# 24V_to_5V.net
KiCad netlist of a schematic drawn in Altium Designer
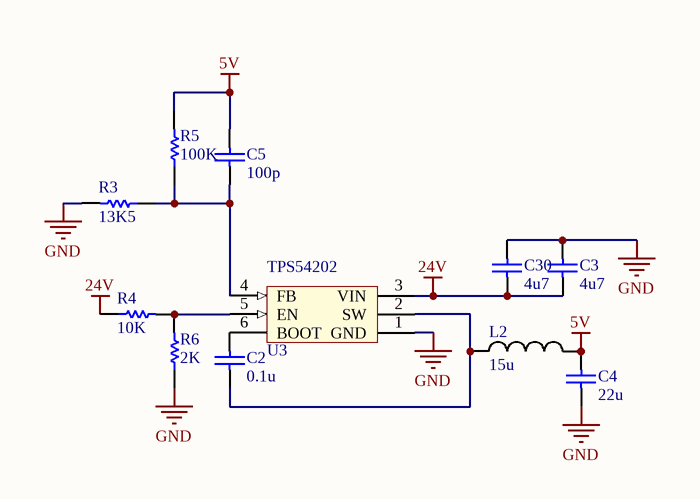
[diagram p0: 24V_to_5V.SchDoc]

(export (version "E")
  (design (tool "Eeschema 10.0.6"))
  (components
    (comp (ref "C2")
      (value "0.1u")
      (footprint "CAPC1608X90N")
      (description "Capacitor")
      (fields (field (name "Comment") "Cap") (field (name "PUBLISHER") "Altium Limited"))
      (libsource (lib "IOBoard_Low") (part "Cap"))
    )
    (comp (ref "C3")
      (value "4u7")
      (footprint "CAPC2012X135N")
      (description "Capacitor")
      (fields (field (name "Comment") "Cap") (field (name "PUBLISHER") "Altium Limited"))
      (libsource (lib "IOBoard_Low") (part "Cap"))
    )
    (comp (ref "C4")
      (value "22u")
      (footprint "CAPC2012X135N")
      (description "Capacitor")
      (fields (field (name "Comment") "Cap") (field (name "PUBLISHER") "Altium Limited"))
      (libsource (lib "IOBoard_Low") (part "Cap"))
    )
    (comp (ref "C5")
      (value "100p")
      (footprint "CAPC1608X90N")
      (description "Capacitor")
      (fields (field (name "Comment") "Cap") (field (name "PUBLISHER") "Altium Limited"))
      (libsource (lib "IOBoard_Low") (part "Cap"))
    )
    (comp (ref "C30")
      (value "4u7")
      (footprint "CAPC2012X135N")
      (description "Capacitor")
      (fields (field (name "Comment") "Cap") (field (name "PUBLISHER") "Altium Limited"))
      (libsource (lib "IOBoard_Low") (part "Cap"))
    )
    (comp (ref "L2")
      (value "15u")
      (footprint "INDC_5.5x5.3x3")
      (description "15uH inductor with 2A saturation current. Dimension is 5.5 * 5.2 * 3 mm^3")
      (fields (field (name "Comment") "15uH inductor"))
      (libsource (lib "IOBoard_Low") (part "INDC_MPX1D0530L150"))
    )
    (comp (ref "R3")
      (value "13K5")
      (footprint "RESC1608X55N")
      (description "Resistor")
      (fields (field (name "Comment") "Res1") (field (name "PUBLISHER") "Altium Limited"))
      (libsource (lib "IOBoard_Low") (part "Res1"))
    )
    (comp (ref "R4")
      (value "10K")
      (footprint "RESC1608X55N")
      (description "Resistor")
      (fields (field (name "Comment") "Res1") (field (name "PUBLISHER") "Altium Limited"))
      (libsource (lib "IOBoard_Low") (part "Res1"))
    )
    (comp (ref "R5")
      (value "100K")
      (footprint "RESC1608X55N")
      (description "Resistor")
      (fields (field (name "Comment") "Res1") (field (name "PUBLISHER") "Altium Limited"))
      (libsource (lib "IOBoard_Low") (part "Res1"))
    )
    (comp (ref "R6")
      (value "2K")
      (footprint "RESC1608X55N")
      (description "Resistor")
      (fields (field (name "Comment") "Res1") (field (name "PUBLISHER") "Altium Limited"))
      (libsource (lib "IOBoard_Low") (part "Res1"))
    )
    (comp (ref "U3")
      (value "TPS54202")
      (footprint "SOT23-6")
      (description "4.5-28V input 2A output step down, EMI Friendly Synchronous Step Down Converter")
      (libsource (lib "IOBoard_Low") (part "TPS54202"))
    )
  )
  (nets
    (net (code "1") (name "5V") (class "Default")
      (node (ref "C4") (pin "2") (pinfunction "2_2") (pintype "passive"))
      (node (ref "C5") (pin "2") (pinfunction "2_2") (pintype "passive"))
      (node (ref "L2") (pin "2") (pinfunction "2_2") (pintype "passive"))
      (node (ref "R5") (pin "2") (pinfunction "2_2") (pintype "passive"))
    )
    (net (code "2") (name "24V") (class "Default")
      (node (ref "C3") (pin "2") (pinfunction "2_2") (pintype "passive"))
      (node (ref "C30") (pin "2") (pinfunction "2_2") (pintype "passive"))
      (node (ref "R4") (pin "1") (pinfunction "1_1") (pintype "passive"))
      (node (ref "U3") (pin "3") (pinfunction "VIN_3") (pintype "power_in"))
    )
    (net (code "3") (name "GND") (class "Default")
      (node (ref "C3") (pin "1") (pinfunction "1_1") (pintype "passive"))
      (node (ref "C30") (pin "1") (pinfunction "1_1") (pintype "passive"))
      (node (ref "C4") (pin "1") (pinfunction "1_1") (pintype "passive"))
      (node (ref "R3") (pin "2") (pinfunction "2_2") (pintype "passive"))
      (node (ref "R6") (pin "1") (pinfunction "1_1") (pintype "passive"))
      (node (ref "U3") (pin "1") (pinfunction "GND_1") (pintype "power_in"))
    )
    (net (code "4") (name "Net-(U3-BOOT)") (class "Default")
      (node (ref "C2") (pin "2") (pinfunction "2_2") (pintype "passive"))
      (node (ref "U3") (pin "6") (pinfunction "BOOT_6") (pintype "passive"))
    )
    (net (code "5") (name "Net-(U3-EN)") (class "Default")
      (node (ref "R4") (pin "2") (pinfunction "2_2") (pintype "passive"))
      (node (ref "R6") (pin "2") (pinfunction "2_2") (pintype "passive"))
      (node (ref "U3") (pin "5") (pinfunction "EN_5") (pintype "input"))
    )
    (net (code "6") (name "Net-(U3-FB)") (class "Default")
      (node (ref "C5") (pin "1") (pinfunction "1_1") (pintype "passive"))
      (node (ref "R3") (pin "1") (pinfunction "1_1") (pintype "passive"))
      (node (ref "R5") (pin "1") (pinfunction "1_1") (pintype "passive"))
      (node (ref "U3") (pin "4") (pinfunction "FB_4") (pintype "input"))
    )
    (net (code "7") (name "Net-(U3-SW)") (class "Default")
      (node (ref "C2") (pin "1") (pinfunction "1_1") (pintype "passive"))
      (node (ref "L2") (pin "1") (pinfunction "1_1") (pintype "passive"))
      (node (ref "U3") (pin "2") (pinfunction "SW_2") (pintype "power_in"))
    )
  )
)
